# OSSISolarX-.net
KiCad netlist of a schematic drawn in EAGLE
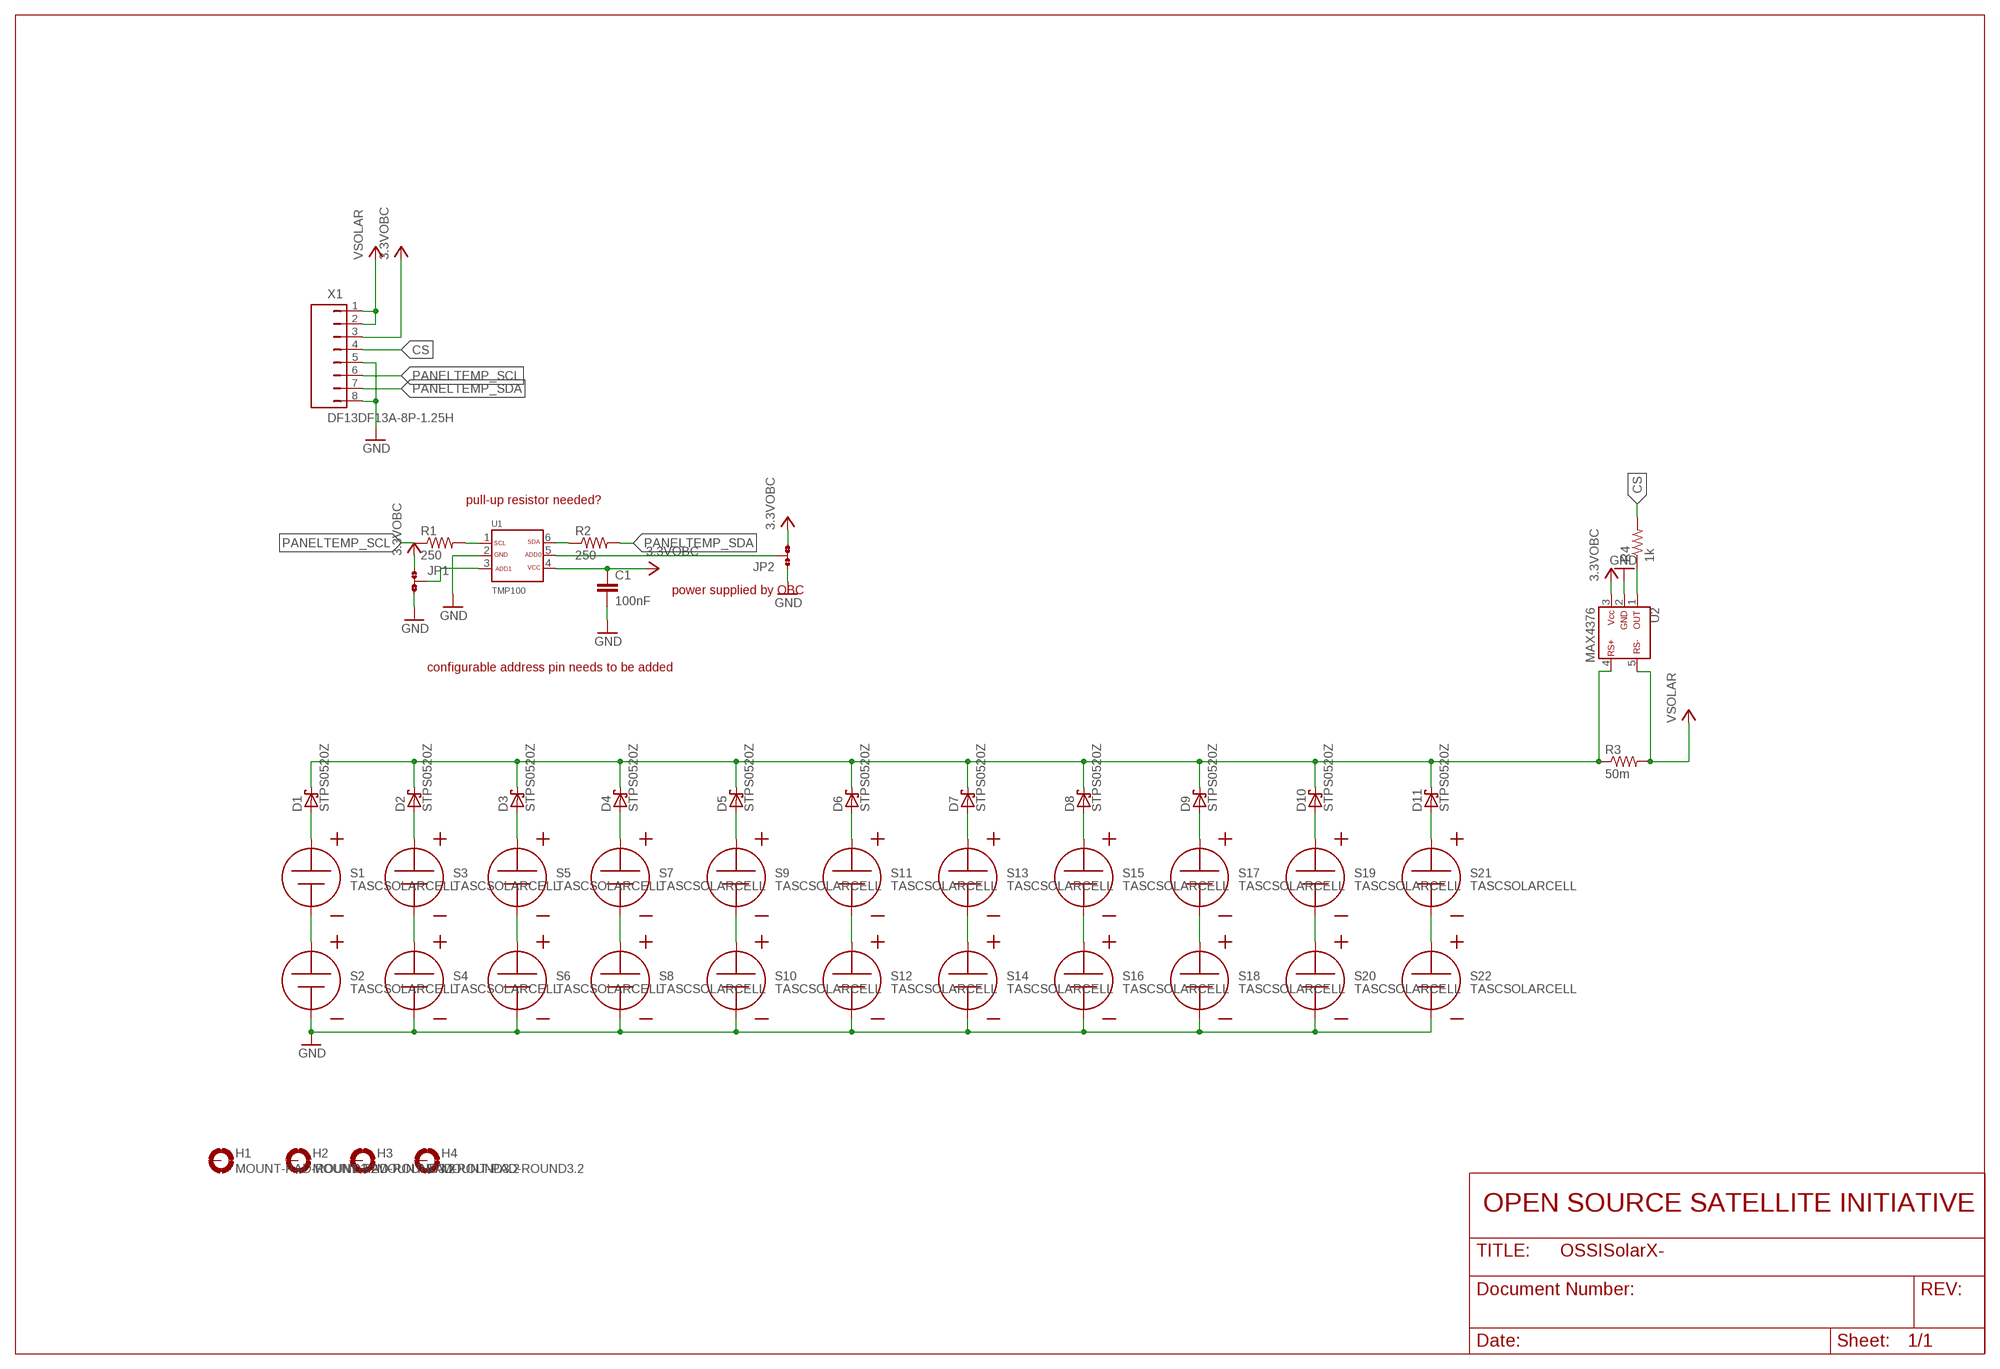
[diagram p0: schematic, sheet 1]

(export (version "E")
  (design (tool "Eeschema 10.0.6"))
  (components
    (comp (ref "C1")
      (value "100nF")
      (footprint "eagle-import:C0603(1608)")
      (libsource (lib "eagle-import") (part "C0603(1608)"))
    )
    (comp (ref "D1")
      (value "STPS0520Z")
      (footprint "eagle-import:SOD-123")
      (libsource (lib "eagle-import") (part "STPS0520Z"))
    )
    (comp (ref "D2")
      (value "STPS0520Z")
      (footprint "eagle-import:SOD-123")
      (libsource (lib "eagle-import") (part "STPS0520Z"))
    )
    (comp (ref "D3")
      (value "STPS0520Z")
      (footprint "eagle-import:SOD-123")
      (libsource (lib "eagle-import") (part "STPS0520Z"))
    )
    (comp (ref "D4")
      (value "STPS0520Z")
      (footprint "eagle-import:SOD-123")
      (libsource (lib "eagle-import") (part "STPS0520Z"))
    )
    (comp (ref "D5")
      (value "STPS0520Z")
      (footprint "eagle-import:SOD-123")
      (libsource (lib "eagle-import") (part "STPS0520Z"))
    )
    (comp (ref "D6")
      (value "STPS0520Z")
      (footprint "eagle-import:SOD-123")
      (libsource (lib "eagle-import") (part "STPS0520Z"))
    )
    (comp (ref "D7")
      (value "STPS0520Z")
      (footprint "eagle-import:SOD-123")
      (libsource (lib "eagle-import") (part "STPS0520Z"))
    )
    (comp (ref "D8")
      (value "STPS0520Z")
      (footprint "eagle-import:SOD-123")
      (libsource (lib "eagle-import") (part "STPS0520Z"))
    )
    (comp (ref "D9")
      (value "STPS0520Z")
      (footprint "eagle-import:SOD-123")
      (libsource (lib "eagle-import") (part "STPS0520Z"))
    )
    (comp (ref "D10")
      (value "STPS0520Z")
      (footprint "eagle-import:SOD-123")
      (libsource (lib "eagle-import") (part "STPS0520Z"))
    )
    (comp (ref "D11")
      (value "STPS0520Z")
      (footprint "eagle-import:SOD-123")
      (libsource (lib "eagle-import") (part "STPS0520Z"))
    )
    (comp (ref "H1")
      (value "MOUNT-PAD-ROUND3.2")
      (footprint "eagle-import:3.2-PAD-ROUND")
      (libsource (lib "eagle-import") (part "MOUNT-PAD-ROUND3.2"))
    )
    (comp (ref "H2")
      (value "MOUNT-PAD-ROUND3.2")
      (footprint "eagle-import:3.2-PAD-ROUND")
      (libsource (lib "eagle-import") (part "MOUNT-PAD-ROUND3.2"))
    )
    (comp (ref "H3")
      (value "MOUNT-PAD-ROUND3.2")
      (footprint "eagle-import:3.2-PAD-ROUND")
      (libsource (lib "eagle-import") (part "MOUNT-PAD-ROUND3.2"))
    )
    (comp (ref "H4")
      (value "MOUNT-PAD-ROUND3.2")
      (footprint "eagle-import:3.2-PAD-ROUND")
      (libsource (lib "eagle-import") (part "MOUNT-PAD-ROUND3.2"))
    )
    (comp (ref "JP1")
      (value "JP2")
      (footprint "eagle-import:JP2SMD0603")
      (libsource (lib "eagle-import") (part "JP2"))
    )
    (comp (ref "JP2")
      (value "JP2")
      (footprint "eagle-import:JP2SMD0603")
      (libsource (lib "eagle-import") (part "JP2"))
    )
    (comp (ref "R1")
      (value "250")
      (footprint "eagle-import:R0603(1608)")
      (libsource (lib "eagle-import") (part "R0603(1608)"))
    )
    (comp (ref "R2")
      (value "250")
      (footprint "eagle-import:R0603(1608)")
      (libsource (lib "eagle-import") (part "R0603(1608)"))
    )
    (comp (ref "R3")
      (value "50m")
      (footprint "eagle-import:WSL1206")
      (libsource (lib "eagle-import") (part "RWSL1206"))
    )
    (comp (ref "R4")
      (value "1k")
      (footprint "eagle-import:R0603(1608)")
      (libsource (lib "eagle-import") (part "R0603(1608)"))
    )
    (comp (ref "S1")
      (value "TASCSOLARCELL")
      (footprint "eagle-import:TASCSOLARCELL")
      (libsource (lib "eagle-import") (part "TASCSOLARCELL"))
    )
    (comp (ref "S2")
      (value "TASCSOLARCELL")
      (footprint "eagle-import:TASCSOLARCELL")
      (libsource (lib "eagle-import") (part "TASCSOLARCELL"))
    )
    (comp (ref "S3")
      (value "TASCSOLARCELL")
      (footprint "eagle-import:TASCSOLARCELL")
      (libsource (lib "eagle-import") (part "TASCSOLARCELL"))
    )
    (comp (ref "S4")
      (value "TASCSOLARCELL")
      (footprint "eagle-import:TASCSOLARCELL")
      (libsource (lib "eagle-import") (part "TASCSOLARCELL"))
    )
    (comp (ref "S5")
      (value "TASCSOLARCELL")
      (footprint "eagle-import:TASCSOLARCELL")
      (libsource (lib "eagle-import") (part "TASCSOLARCELL"))
    )
    (comp (ref "S6")
      (value "TASCSOLARCELL")
      (footprint "eagle-import:TASCSOLARCELL")
      (libsource (lib "eagle-import") (part "TASCSOLARCELL"))
    )
    (comp (ref "S7")
      (value "TASCSOLARCELL")
      (footprint "eagle-import:TASCSOLARCELL")
      (libsource (lib "eagle-import") (part "TASCSOLARCELL"))
    )
    (comp (ref "S8")
      (value "TASCSOLARCELL")
      (footprint "eagle-import:TASCSOLARCELL")
      (libsource (lib "eagle-import") (part "TASCSOLARCELL"))
    )
    (comp (ref "S9")
      (value "TASCSOLARCELL")
      (footprint "eagle-import:TASCSOLARCELL")
      (libsource (lib "eagle-import") (part "TASCSOLARCELL"))
    )
    (comp (ref "S10")
      (value "TASCSOLARCELL")
      (footprint "eagle-import:TASCSOLARCELL")
      (libsource (lib "eagle-import") (part "TASCSOLARCELL"))
    )
    (comp (ref "S11")
      (value "TASCSOLARCELL")
      (footprint "eagle-import:TASCSOLARCELL")
      (libsource (lib "eagle-import") (part "TASCSOLARCELL"))
    )
    (comp (ref "S12")
      (value "TASCSOLARCELL")
      (footprint "eagle-import:TASCSOLARCELL")
      (libsource (lib "eagle-import") (part "TASCSOLARCELL"))
    )
    (comp (ref "S13")
      (value "TASCSOLARCELL")
      (footprint "eagle-import:TASCSOLARCELL")
      (libsource (lib "eagle-import") (part "TASCSOLARCELL"))
    )
    (comp (ref "S14")
      (value "TASCSOLARCELL")
      (footprint "eagle-import:TASCSOLARCELL")
      (libsource (lib "eagle-import") (part "TASCSOLARCELL"))
    )
    (comp (ref "S15")
      (value "TASCSOLARCELL")
      (footprint "eagle-import:TASCSOLARCELL")
      (libsource (lib "eagle-import") (part "TASCSOLARCELL"))
    )
    (comp (ref "S16")
      (value "TASCSOLARCELL")
      (footprint "eagle-import:TASCSOLARCELL")
      (libsource (lib "eagle-import") (part "TASCSOLARCELL"))
    )
    (comp (ref "S17")
      (value "TASCSOLARCELL")
      (footprint "eagle-import:TASCSOLARCELL")
      (libsource (lib "eagle-import") (part "TASCSOLARCELL"))
    )
    (comp (ref "S18")
      (value "TASCSOLARCELL")
      (footprint "eagle-import:TASCSOLARCELL")
      (libsource (lib "eagle-import") (part "TASCSOLARCELL"))
    )
    (comp (ref "S19")
      (value "TASCSOLARCELL")
      (footprint "eagle-import:TASCSOLARCELL")
      (libsource (lib "eagle-import") (part "TASCSOLARCELL"))
    )
    (comp (ref "S20")
      (value "TASCSOLARCELL")
      (footprint "eagle-import:TASCSOLARCELL")
      (libsource (lib "eagle-import") (part "TASCSOLARCELL"))
    )
    (comp (ref "S21")
      (value "TASCSOLARCELL")
      (footprint "eagle-import:TASCSOLARCELL")
      (libsource (lib "eagle-import") (part "TASCSOLARCELL"))
    )
    (comp (ref "S22")
      (value "TASCSOLARCELL")
      (footprint "eagle-import:TASCSOLARCELL")
      (libsource (lib "eagle-import") (part "TASCSOLARCELL"))
    )
    (comp (ref "U1")
      (value "TMP100")
      (footprint "eagle-import:SOT23-6DBV")
      (libsource (lib "eagle-import") (part "TMP100"))
    )
    (comp (ref "U2")
      (value "MAX4376")
      (footprint "eagle-import:SOT23-5DBV")
      (libsource (lib "eagle-import") (part "MAX4376"))
    )
    (comp (ref "X1")
      (value "DF13DF13A-8P-1.25H")
      (footprint "eagle-import:DF13A-8P")
      (libsource (lib "eagle-import") (part "DF13DF13A-8P-1.25H"))
    )
  )
  (nets
    (net (code "1") (name "3.3VOBC") (class "Default")
      (node (ref "C1") (pin "1") (pinfunction "1_1") (pintype "passive"))
      (node (ref "JP1") (pin "1") (pinfunction "1_1") (pintype "passive"))
      (node (ref "JP2") (pin "3") (pinfunction "3_3") (pintype "passive"))
      (node (ref "U1") (pin "4") (pinfunction "4_4") (pintype "bidirectional"))
      (node (ref "U2") (pin "3") (pinfunction "P$3_3") (pintype "power_in"))
      (node (ref "X1") (pin "3") (pinfunction "3_3") (pintype "passive"))
    )
    (net (code "2") (name "CS") (class "Default")
      (node (ref "R4") (pin "2") (pinfunction "2_2") (pintype "passive"))
      (node (ref "X1") (pin "4") (pinfunction "4_4") (pintype "passive"))
    )
    (net (code "3") (name "GND") (class "Default")
      (node (ref "C1") (pin "2") (pinfunction "2_2") (pintype "passive"))
      (node (ref "JP1") (pin "3") (pinfunction "3_3") (pintype "passive"))
      (node (ref "JP2") (pin "1") (pinfunction "1_1") (pintype "passive"))
      (node (ref "S10") (pin "N") (pinfunction "N_N") (pintype "power_in"))
      (node (ref "S12") (pin "N") (pinfunction "N_N") (pintype "power_in"))
      (node (ref "S14") (pin "N") (pinfunction "N_N") (pintype "power_in"))
      (node (ref "S16") (pin "N") (pinfunction "N_N") (pintype "power_in"))
      (node (ref "S18") (pin "N") (pinfunction "N_N") (pintype "power_in"))
      (node (ref "S2") (pin "N") (pinfunction "N_N") (pintype "power_in"))
      (node (ref "S20") (pin "N") (pinfunction "N_N") (pintype "power_in"))
      (node (ref "S22") (pin "N") (pinfunction "N_N") (pintype "power_in"))
      (node (ref "S4") (pin "N") (pinfunction "N_N") (pintype "power_in"))
      (node (ref "S6") (pin "N") (pinfunction "N_N") (pintype "power_in"))
      (node (ref "S8") (pin "N") (pinfunction "N_N") (pintype "power_in"))
      (node (ref "U1") (pin "2") (pinfunction "2_2") (pintype "bidirectional"))
      (node (ref "U2") (pin "2") (pinfunction "P$2_2") (pintype "power_in"))
      (node (ref "X1") (pin "5") (pinfunction "5_5") (pintype "passive"))
      (node (ref "X1") (pin "8") (pinfunction "8_8") (pintype "passive"))
    )
    (net (code "4") (name "Net-(D1-PadA)") (class "Default")
      (node (ref "D1") (pin "A") (pinfunction "A_A") (pintype "passive"))
      (node (ref "S1") (pin "P") (pinfunction "P_P") (pintype "power_in"))
    )
    (net (code "5") (name "Net-(D2-PadA)") (class "Default")
      (node (ref "D2") (pin "A") (pinfunction "A_A") (pintype "passive"))
      (node (ref "S3") (pin "P") (pinfunction "P_P") (pintype "power_in"))
    )
    (net (code "6") (name "Net-(D3-PadA)") (class "Default")
      (node (ref "D3") (pin "A") (pinfunction "A_A") (pintype "passive"))
      (node (ref "S5") (pin "P") (pinfunction "P_P") (pintype "power_in"))
    )
    (net (code "7") (name "Net-(D4-PadA)") (class "Default")
      (node (ref "D4") (pin "A") (pinfunction "A_A") (pintype "passive"))
      (node (ref "S7") (pin "P") (pinfunction "P_P") (pintype "power_in"))
    )
    (net (code "8") (name "Net-(D5-PadA)") (class "Default")
      (node (ref "D5") (pin "A") (pinfunction "A_A") (pintype "passive"))
      (node (ref "S9") (pin "P") (pinfunction "P_P") (pintype "power_in"))
    )
    (net (code "9") (name "Net-(D6-PadA)") (class "Default")
      (node (ref "D6") (pin "A") (pinfunction "A_A") (pintype "passive"))
      (node (ref "S11") (pin "P") (pinfunction "P_P") (pintype "power_in"))
    )
    (net (code "10") (name "Net-(D7-PadA)") (class "Default")
      (node (ref "D7") (pin "A") (pinfunction "A_A") (pintype "passive"))
      (node (ref "S13") (pin "P") (pinfunction "P_P") (pintype "power_in"))
    )
    (net (code "11") (name "Net-(D8-PadA)") (class "Default")
      (node (ref "D8") (pin "A") (pinfunction "A_A") (pintype "passive"))
      (node (ref "S15") (pin "P") (pinfunction "P_P") (pintype "power_in"))
    )
    (net (code "12") (name "Net-(D9-PadA)") (class "Default")
      (node (ref "D9") (pin "A") (pinfunction "A_A") (pintype "passive"))
      (node (ref "S17") (pin "P") (pinfunction "P_P") (pintype "power_in"))
    )
    (net (code "13") (name "Net-(D10-PadA)") (class "Default")
      (node (ref "D10") (pin "A") (pinfunction "A_A") (pintype "passive"))
      (node (ref "S19") (pin "P") (pinfunction "P_P") (pintype "power_in"))
    )
    (net (code "14") (name "Net-(D11-PadA)") (class "Default")
      (node (ref "D11") (pin "A") (pinfunction "A_A") (pintype "passive"))
      (node (ref "S21") (pin "P") (pinfunction "P_P") (pintype "power_in"))
    )
    (net (code "15") (name "Net-(JP1-Pad2)") (class "Default")
      (node (ref "JP1") (pin "2") (pinfunction "2_2") (pintype "passive"))
      (node (ref "U1") (pin "3") (pinfunction "3_3") (pintype "bidirectional"))
    )
    (net (code "16") (name "Net-(JP2-Pad2)") (class "Default")
      (node (ref "JP2") (pin "2") (pinfunction "2_2") (pintype "passive"))
      (node (ref "U1") (pin "5") (pinfunction "5_5") (pintype "bidirectional"))
    )
    (net (code "17") (name "Net-(R1-Pad2)") (class "Default")
      (node (ref "R1") (pin "2") (pinfunction "2_2") (pintype "passive"))
      (node (ref "U1") (pin "1") (pinfunction "1_1") (pintype "bidirectional"))
    )
    (net (code "18") (name "Net-(R2-Pad1)") (class "Default")
      (node (ref "R2") (pin "1") (pinfunction "1_1") (pintype "passive"))
      (node (ref "U1") (pin "6") (pinfunction "6_6") (pintype "bidirectional"))
    )
    (net (code "19") (name "Net-(R3-1)") (class "Default")
      (node (ref "D1") (pin "C") (pinfunction "C_C") (pintype "passive"))
      (node (ref "D10") (pin "C") (pinfunction "C_C") (pintype "passive"))
      (node (ref "D11") (pin "C") (pinfunction "C_C") (pintype "passive"))
      (node (ref "D2") (pin "C") (pinfunction "C_C") (pintype "passive"))
      (node (ref "D3") (pin "C") (pinfunction "C_C") (pintype "passive"))
      (node (ref "D4") (pin "C") (pinfunction "C_C") (pintype "passive"))
      (node (ref "D5") (pin "C") (pinfunction "C_C") (pintype "passive"))
      (node (ref "D6") (pin "C") (pinfunction "C_C") (pintype "passive"))
      (node (ref "D7") (pin "C") (pinfunction "C_C") (pintype "passive"))
      (node (ref "D8") (pin "C") (pinfunction "C_C") (pintype "passive"))
      (node (ref "D9") (pin "C") (pinfunction "C_C") (pintype "passive"))
      (node (ref "R3") (pin "P$1") (pinfunction "1_P$1") (pintype "passive"))
      (node (ref "U2") (pin "4") (pinfunction "P$4_4") (pintype "input"))
    )
    (net (code "20") (name "Net-(S1-PadN)") (class "Default")
      (node (ref "S1") (pin "N") (pinfunction "N_N") (pintype "power_in"))
      (node (ref "S2") (pin "P") (pinfunction "P_P") (pintype "power_in"))
    )
    (net (code "21") (name "Net-(S3-PadN)") (class "Default")
      (node (ref "S3") (pin "N") (pinfunction "N_N") (pintype "power_in"))
      (node (ref "S4") (pin "P") (pinfunction "P_P") (pintype "power_in"))
    )
    (net (code "22") (name "Net-(S5-PadN)") (class "Default")
      (node (ref "S5") (pin "N") (pinfunction "N_N") (pintype "power_in"))
      (node (ref "S6") (pin "P") (pinfunction "P_P") (pintype "power_in"))
    )
    (net (code "23") (name "Net-(S7-PadN)") (class "Default")
      (node (ref "S7") (pin "N") (pinfunction "N_N") (pintype "power_in"))
      (node (ref "S8") (pin "P") (pinfunction "P_P") (pintype "power_in"))
    )
    (net (code "24") (name "Net-(S10-PadP)") (class "Default")
      (node (ref "S10") (pin "P") (pinfunction "P_P") (pintype "power_in"))
      (node (ref "S9") (pin "N") (pinfunction "N_N") (pintype "power_in"))
    )
    (net (code "25") (name "Net-(S11-PadN)") (class "Default")
      (node (ref "S11") (pin "N") (pinfunction "N_N") (pintype "power_in"))
      (node (ref "S12") (pin "P") (pinfunction "P_P") (pintype "power_in"))
    )
    (net (code "26") (name "Net-(S13-PadN)") (class "Default")
      (node (ref "S13") (pin "N") (pinfunction "N_N") (pintype "power_in"))
      (node (ref "S14") (pin "P") (pinfunction "P_P") (pintype "power_in"))
    )
    (net (code "27") (name "Net-(S15-PadN)") (class "Default")
      (node (ref "S15") (pin "N") (pinfunction "N_N") (pintype "power_in"))
      (node (ref "S16") (pin "P") (pinfunction "P_P") (pintype "power_in"))
    )
    (net (code "28") (name "Net-(S17-PadN)") (class "Default")
      (node (ref "S17") (pin "N") (pinfunction "N_N") (pintype "power_in"))
      (node (ref "S18") (pin "P") (pinfunction "P_P") (pintype "power_in"))
    )
    (net (code "29") (name "Net-(S19-PadN)") (class "Default")
      (node (ref "S19") (pin "N") (pinfunction "N_N") (pintype "power_in"))
      (node (ref "S20") (pin "P") (pinfunction "P_P") (pintype "power_in"))
    )
    (net (code "30") (name "Net-(S21-PadN)") (class "Default")
      (node (ref "S21") (pin "N") (pinfunction "N_N") (pintype "power_in"))
      (node (ref "S22") (pin "P") (pinfunction "P_P") (pintype "power_in"))
    )
    (net (code "31") (name "Net-(U2-P$1)") (class "Default")
      (node (ref "R4") (pin "1") (pinfunction "1_1") (pintype "passive"))
      (node (ref "U2") (pin "1") (pinfunction "P$1_1") (pintype "output"))
    )
    (net (code "32") (name "PANELTEMP_SCL") (class "Default")
      (node (ref "R1") (pin "1") (pinfunction "1_1") (pintype "passive"))
      (node (ref "X1") (pin "6") (pinfunction "6_6") (pintype "passive"))
    )
    (net (code "33") (name "PANELTEMP_SDA") (class "Default")
      (node (ref "R2") (pin "2") (pinfunction "2_2") (pintype "passive"))
      (node (ref "X1") (pin "7") (pinfunction "7_7") (pintype "passive"))
    )
    (net (code "34") (name "VSOLAR") (class "Default")
      (node (ref "R3") (pin "P$2") (pinfunction "2_P$2") (pintype "passive"))
      (node (ref "U2") (pin "5") (pinfunction "P$5_5") (pintype "input"))
      (node (ref "X1") (pin "1") (pinfunction "1_1") (pintype "passive"))
      (node (ref "X1") (pin "2") (pinfunction "2_2") (pintype "passive"))
    )
    (net (code "35") (name "unconnected-(H1-MOUNT-PadB3,2)") (class "Default")
      (node (ref "H1") (pin "B3,2") (pinfunction "MOUNT_B3,2") (pintype "passive"))
    )
    (net (code "36") (name "unconnected-(H2-MOUNT-PadB3,2)") (class "Default")
      (node (ref "H2") (pin "B3,2") (pinfunction "MOUNT_B3,2") (pintype "passive"))
    )
    (net (code "37") (name "unconnected-(H3-MOUNT-PadB3,2)") (class "Default")
      (node (ref "H3") (pin "B3,2") (pinfunction "MOUNT_B3,2") (pintype "passive"))
    )
    (net (code "38") (name "unconnected-(H4-MOUNT-PadB3,2)") (class "Default")
      (node (ref "H4") (pin "B3,2") (pinfunction "MOUNT_B3,2") (pintype "passive"))
    )
  )
)
